# Sheet8.net
KiCad netlist of a schematic drawn in Altium Designer
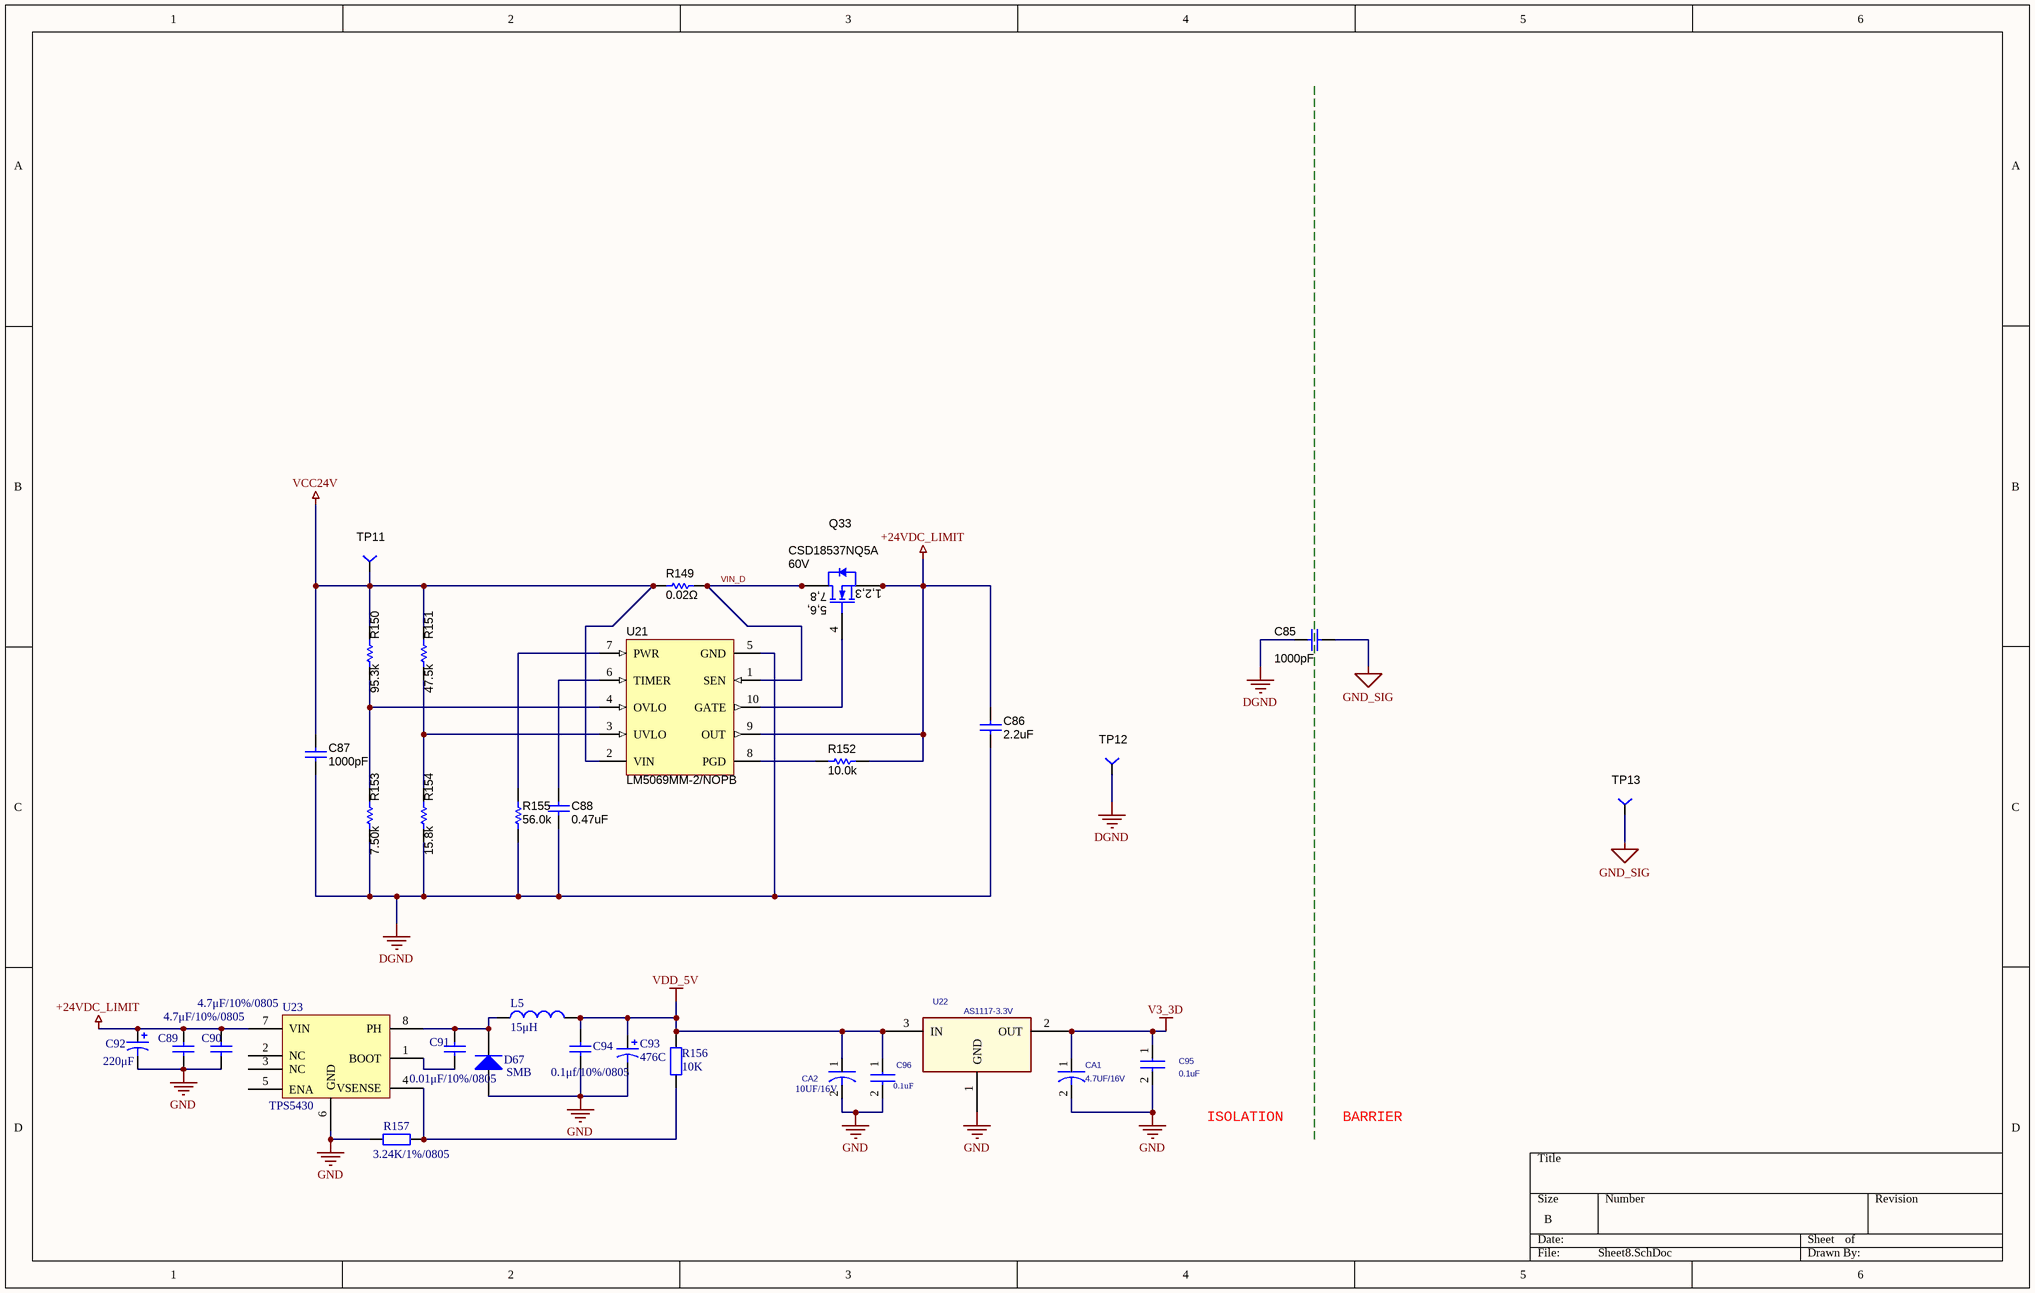
[diagram p0: Sheet8.SchDoc]

(export (version "E")
  (design (tool "Eeschema 10.0.6"))
  (components
    (comp (ref "C85")
      (value "1000pF")
      (footprint "1206")
      (description "CAP, CERM, 1000pF, 2KV 10% X7R 1206")
      (fields
        (field (name "PARTNUMBER") "202R18W102KV4E")
        (field (name "MANUFACTURER") "Johanson Dielectrics Inc")
        (field (name "PUBLISHER") "Texas Instruments")
      )
      (libsource (lib "TI-INDIA-ALTIUM") (part "202R18W102KV4E"))
    )
    (comp (ref "C86")
      (value "GRM32ER72A225KA35L")
      (footprint "1210")
      (description "CAP, CERM, 2.2uF, 100V, +/-10%, X7R, 1210")
      (fields
        (field (name "VALUEDISPLAYED") "2.2uF")
        (field (name "MANUFACTURER") "MuRata")
        (field (name "PUBLISHER") "Texas Instruments")
      )
      (libsource (lib "Capacitor_Ceramic") (part "GRM32ER72A225KA35L"))
    )
    (comp (ref "C87")
      (value "06031C102JAT2A")
      (footprint "0805_cap")
      (description "CAP, CERM, 1000pF, 100V, +/-5%, X7R, 0603")
      (fields
        (field (name "VALUEDISPLAYED") "1000pF")
        (field (name "MANUFACTURER") "AVX")
        (field (name "PUBLISHER") "Texas Instruments")
      )
      (libsource (lib "Capacitor_Ceramic") (part "06031C102JAT2A"))
    )
    (comp (ref "C88")
      (value "UMK107ABJ474KA-T")
      (footprint "0805_cap")
      (description "CAP, CERM, 0.47uF, 50V, 10%, X5R, 0603")
      (fields
        (field (name "MANUFACTURER") "Taiyo Yuden")
        (field (name "VALUEDISPLAYED") "0.47uF")
        (field (name "PUBLISHER") "Texas Instruments")
      )
      (libsource (lib "TI-INDIA-ALTIUM") (part "UMK107ABJ474KA-T"))
    )
    (comp (ref "C89")
      (value "4.7μF/10%/0805")
      (footprint "0805_CAP")
      (description "Capacitor")
      (fields (field (name "PUBLISHER") "Altium Limited"))
      (libsource (lib "Miscellaneous Devices") (part "Cap"))
    )
    (comp (ref "C90")
      (value "4.7μF/10%/0805")
      (footprint "0805_CAP")
      (description "Capacitor")
      (fields (field (name "PUBLISHER") "Altium Limited"))
      (libsource (lib "Miscellaneous Devices") (part "Cap"))
    )
    (comp (ref "C91")
      (value "0.01μF/10%/0805")
      (footprint "0805_CAP")
      (description "Capacitor")
      (fields (field (name "PUBLISHER") "Altium Limited"))
      (libsource (lib "Miscellaneous Devices") (part "Cap"))
    )
    (comp (ref "C92")
      (value "220μF")
      (footprint "CZ3.0/6.5")
      (description "Polarized Capacitor (Radial)")
      (fields (field (name "PUBLISHER") "Altium Limited"))
      (libsource (lib "Miscellaneous Devices") (part "Cap Pol1"))
    )
    (comp (ref "C93")
      (value "476C")
      (footprint "7343-43")
      (description "Polarized Capacitor (Radial)")
      (fields (field (name "PUBLISHER") "Altium Limited"))
      (libsource (lib "Miscellaneous Devices") (part "Cap Pol1"))
    )
    (comp (ref "C94")
      (value "0.1μf/10%/0805")
      (footprint "0805_CAP")
      (description "Capacitor")
      (fields (field (name "PUBLISHER") "Altium Limited"))
      (libsource (lib "Miscellaneous Devices") (part "Cap"))
    )
    (comp (ref "C95") (value "0.1uF") (footprint "0805_CAP") (libsource (lib "v3") (part "C")))
    (comp (ref "C96") (value "0.1uF") (footprint "0805_CAP") (libsource (lib "v3") (part "C")))
    (comp (ref "CA1") (value "4.7UF/16V") (footprint "3528cap") (libsource (lib "v3") (part "ECAP")))
    (comp (ref "CA2") (value "10UF/16V") (footprint "3528cap") (libsource (lib "v3") (part "ECAP")))
    (comp (ref "D67")
      (value "SMB")
      (footprint "SMB")
      (description "3 Amp Medium Power Silicon Rectifier Diode")
      (fields (field (name "PUBLISHER") "Altium Limited"))
      (libsource (lib "Miscellaneous Devices") (part "Diode 1N5408"))
    )
    (comp (ref "L5")
      (value "15μH")
      (footprint "GSDS104C2")
      (description "Inductor")
      (fields (field (name "PUBLISHER") "Altium Limited"))
      (libsource (lib "Miscellaneous Devices") (part "Inductor"))
    )
    (comp (ref "Q33")
      (value "CSD18537NQ5A")
      (footprint "TRANS_NexFET_Q5A")
      (description "MOSFET, N-CH, 60V, 50A, SON 5x6mm")
      (fields
        (field (name "ALTIUM_VALUE") "60V")
        (field (name "MANUFACTURER") "Texas Instruments")
        (field (name "PUBLISHER") "Texas Instruments")
      )
      (libsource (lib "FETs") (part "CSD18537NQ5A"))
    )
    (comp (ref "R149")
      (value "0.02Ω")
      (footprint "1206")
      (description "RES, 0.02 ohm, 1%, 1W, 1206")
      (fields
        (field (name "PARTNUMBER") "PRL1632-R020-F-T1")
        (field (name "MANUFACTURER") "Susumu Co Ltd")
        (field (name "PUBLISHER") "Texas Instruments")
      )
      (libsource (lib "Resistor_1206") (part "PRL1632-R020-F-T1"))
    )
    (comp (ref "R150")
      (value "95.3k")
      (footprint "0805")
      (description "RES, 95.3k ohm, 1%, 0.1W, 0603")
      (fields
        (field (name "PARTNUMBER") "CRCW060395K3FKEA")
        (field (name "MANUFACTURER") "Vishay-Dale")
        (field (name "PUBLISHER") "Texas Instruments")
      )
      (libsource (lib "Resistor_0603") (part "CRCW060395K3FKEA"))
    )
    (comp (ref "R151")
      (value "47.5k")
      (footprint "0805")
      (description "RES, 47.5k ohm, 1%, 0.1W, 0603")
      (fields
        (field (name "PARTNUMBER") "CRCW060347K5FKEA")
        (field (name "MANUFACTURER") "Vishay-Dale")
        (field (name "PUBLISHER") "Texas Instruments")
      )
      (libsource (lib "Resistor_0603") (part "CRCW060347K5FKEA"))
    )
    (comp (ref "R152")
      (value "10.0k")
      (footprint "0805")
      (description "RES, 10.0k ohm, 1%, 0.1W, 0603")
      (fields
        (field (name "PARTNUMBER") "CRCW060310K0FKEA")
        (field (name "MANUFACTURER") "Vishay-Dale")
        (field (name "PUBLISHER") "Texas Instruments")
      )
      (libsource (lib "Resistor_0603") (part "CRCW060310K0FKEA"))
    )
    (comp (ref "R153")
      (value "7.50k")
      (footprint "0805")
      (description "RES, 7.50k ohm, 1%, 0.1W, 0603")
      (fields
        (field (name "PARTNUMBER") "CRCW06037K50FKEA")
        (field (name "MANUFACTURER") "Vishay-Dale")
        (field (name "PUBLISHER") "Texas Instruments")
      )
      (libsource (lib "Resistor_0603") (part "CRCW06037K50FKEA"))
    )
    (comp (ref "R154")
      (value "15.8k")
      (footprint "0805")
      (description "RES, 15.8k ohm, 1%, 0.1W, 0603")
      (fields
        (field (name "PARTNUMBER") "CRCW060315K8FKEA")
        (field (name "MANUFACTURER") "Vishay-Dale")
        (field (name "PUBLISHER") "Texas Instruments")
      )
      (libsource (lib "Resistor_0603") (part "CRCW060315K8FKEA"))
    )
    (comp (ref "R155")
      (value "56.0k")
      (footprint "0805")
      (description "RES, 56.0k ohm, 0.1%, 0.1W, 0603")
      (fields
        (field (name "PARTNUMBER") "RG1608P-563-B-T5")
        (field (name "MANUFACTURER") "Susumu Co Ltd")
        (field (name "PUBLISHER") "Texas Instruments")
      )
      (libsource (lib "Resistor_0603") (part "RG1608P-563-B-T5"))
    )
    (comp (ref "R156")
      (value "10K")
      (footprint "0805")
      (description "Resistor")
      (fields (field (name "PUBLISHER") "Altium Limited"))
      (libsource (lib "Miscellaneous Devices") (part "Res2"))
    )
    (comp (ref "R157")
      (value "3.24K/1%/0805")
      (footprint "0805")
      (description "Resistor")
      (fields (field (name "PUBLISHER") "Altium Limited"))
      (libsource (lib "") (part "Res2_1"))
    )
    (comp (ref "TP11")
      (value "TP-040_RND")
      (footprint "TP-040_RND")
      (description "Test Point, O.040 Hole")
      (fields (field (name "MANUFACTURER") "Standard"))
      (libsource (lib "PADSlegacy_Hardware") (part "TP-040_RND"))
    )
    (comp (ref "TP12")
      (value "TP-040_RND")
      (footprint "TP-040_RND")
      (description "Test Point, O.040 Hole")
      (fields (field (name "MANUFACTURER") "Standard"))
      (libsource (lib "PADSlegacy_Hardware") (part "TP-040_RND"))
    )
    (comp (ref "TP13")
      (value "TP-040_RND")
      (footprint "TP-040_RND")
      (description "Test Point, O.040 Hole")
      (fields (field (name "MANUFACTURER") "Standard"))
      (libsource (lib "PADSlegacy_Hardware") (part "TP-040_RND"))
    )
    (comp (ref "U21")
      (value "LM5069MM-2/NOPB")
      (footprint "MUB10A_N")
      (fields
        (field (name "MANUFACTURER") "National Semiconductor")
        (field (name "PUBLISHER") "Altium Limited")
      )
      (libsource (lib "NSC MiscPower") (part "LM5069MM-2/NOPB"))
    )
    (comp (ref "U22") (value "AS1117-3.3V") (libsource (lib "v3") (part "AS1117")))
    (comp (ref "U23") (value "TPS5430") (footprint "SO-G8") (libsource (lib "SCHLIBRARIES") (part "TPS5430")))
  )
  (nets
    (net (code "1") (name "+24VDC_LIMIT") (class "Default")
      (node (ref "C86") (pin "1") (pinfunction "1_1") (pintype "passive"))
      (node (ref "C89") (pin "2") (pinfunction "2_2") (pintype "passive"))
      (node (ref "C90") (pin "2") (pinfunction "2_2") (pintype "passive"))
      (node (ref "C92") (pin "1") (pinfunction "1_1") (pintype "passive"))
      (node (ref "Q33") (pin "1") (pinfunction "S_1") (pintype "passive"))
      (node (ref "Q33") (pin "2") (pinfunction "S_2") (pintype "passive"))
      (node (ref "Q33") (pin "3") (pinfunction "S_3") (pintype "passive"))
      (node (ref "R152") (pin "1") (pinfunction "1_1") (pintype "passive"))
      (node (ref "U21") (pin "9") (pinfunction "OUT_9") (pintype "output"))
      (node (ref "U23") (pin "7") (pinfunction "VIN_7") (pintype "passive"))
    )
    (net (code "2") (name "/VIN_D") (class "Default")
      (node (ref "Q33") (pin "5") (pinfunction "D_5") (pintype "passive"))
      (node (ref "Q33") (pin "6") (pinfunction "D_6") (pintype "passive"))
      (node (ref "Q33") (pin "7") (pinfunction "D_7") (pintype "passive"))
      (node (ref "Q33") (pin "8") (pinfunction "D_8") (pintype "passive"))
      (node (ref "Q33") (pin "9") (pinfunction "D_9") (pintype "passive"))
      (node (ref "R149") (pin "2") (pinfunction "2_2") (pintype "passive"))
      (node (ref "U21") (pin "1") (pinfunction "SEN_1") (pintype "input"))
    )
    (net (code "3") (name "DGND") (class "Default")
      (node (ref "C85") (pin "1") (pinfunction "1_1") (pintype "passive"))
      (node (ref "C86") (pin "2") (pinfunction "2_2") (pintype "passive"))
      (node (ref "C87") (pin "2") (pinfunction "2_2") (pintype "passive"))
      (node (ref "C88") (pin "2") (pinfunction "2_2") (pintype "passive"))
      (node (ref "R153") (pin "1") (pinfunction "1_1") (pintype "passive"))
      (node (ref "R154") (pin "1") (pinfunction "1_1") (pintype "passive"))
      (node (ref "R155") (pin "1") (pinfunction "1_1") (pintype "passive"))
      (node (ref "TP12") (pin "1") (pinfunction "1_1") (pintype "passive"))
      (node (ref "U21") (pin "5") (pinfunction "GND_5") (pintype "power_in"))
    )
    (net (code "4") (name "GND") (class "Default")
      (node (ref "C89") (pin "1") (pinfunction "1_1") (pintype "passive"))
      (node (ref "C90") (pin "1") (pinfunction "1_1") (pintype "passive"))
      (node (ref "C92") (pin "2") (pinfunction "2_2") (pintype "passive"))
      (node (ref "C93") (pin "2") (pinfunction "2_2") (pintype "passive"))
      (node (ref "C94") (pin "1") (pinfunction "1_1") (pintype "passive"))
      (node (ref "C95") (pin "2") (pinfunction "2_2") (pintype "passive"))
      (node (ref "C96") (pin "2") (pinfunction "2_2") (pintype "passive"))
      (node (ref "CA1") (pin "2") (pinfunction "2_2") (pintype "passive"))
      (node (ref "CA2") (pin "2") (pinfunction "2_2") (pintype "passive"))
      (node (ref "D67") (pin "1") (pinfunction "A_1") (pintype "passive"))
      (node (ref "R157") (pin "2") (pinfunction "2_2") (pintype "passive"))
      (node (ref "U22") (pin "1") (pinfunction "GND_1") (pintype "passive"))
      (node (ref "U23") (pin "6") (pinfunction "GND_6") (pintype "passive"))
    )
    (net (code "5") (name "GND_SIG") (class "Default")
      (node (ref "C85") (pin "2") (pinfunction "2_2") (pintype "passive"))
      (node (ref "TP13") (pin "1") (pinfunction "1_1") (pintype "passive"))
    )
    (net (code "6") (name "Net-(D67-K)") (class "Default")
      (node (ref "C91") (pin "2") (pinfunction "2_2") (pintype "passive"))
      (node (ref "D67") (pin "2") (pinfunction "K_2") (pintype "passive"))
      (node (ref "L5") (pin "1") (pinfunction "1_1") (pintype "passive"))
      (node (ref "U23") (pin "8") (pinfunction "PH_8") (pintype "passive"))
    )
    (net (code "7") (name "Net-(Q33-G)") (class "Default")
      (node (ref "Q33") (pin "4") (pinfunction "G_4") (pintype "passive"))
      (node (ref "U21") (pin "10") (pinfunction "GATE_10") (pintype "output"))
    )
    (net (code "8") (name "Net-(U21-OVLO)") (class "Default")
      (node (ref "R150") (pin "1") (pinfunction "1_1") (pintype "passive"))
      (node (ref "R153") (pin "2") (pinfunction "2_2") (pintype "passive"))
      (node (ref "U21") (pin "4") (pinfunction "OVLO_4") (pintype "input"))
    )
    (net (code "9") (name "Net-(U21-PGD)") (class "Default")
      (node (ref "R152") (pin "2") (pinfunction "2_2") (pintype "passive"))
      (node (ref "U21") (pin "8") (pinfunction "PGD_8") (pintype "open_collector"))
    )
    (net (code "10") (name "Net-(U21-PWR)") (class "Default")
      (node (ref "R155") (pin "2") (pinfunction "2_2") (pintype "passive"))
      (node (ref "U21") (pin "7") (pinfunction "PWR_7") (pintype "input"))
    )
    (net (code "11") (name "Net-(U21-TIMER)") (class "Default")
      (node (ref "C88") (pin "1") (pinfunction "1_1") (pintype "passive"))
      (node (ref "U21") (pin "6") (pinfunction "TIMER_6") (pintype "input"))
    )
    (net (code "12") (name "Net-(U21-UVLO)") (class "Default")
      (node (ref "R151") (pin "1") (pinfunction "1_1") (pintype "passive"))
      (node (ref "R154") (pin "2") (pinfunction "2_2") (pintype "passive"))
      (node (ref "U21") (pin "3") (pinfunction "UVLO_3") (pintype "input"))
    )
    (net (code "13") (name "Net-(U23-BOOT)") (class "Default")
      (node (ref "C91") (pin "1") (pinfunction "1_1") (pintype "passive"))
      (node (ref "U23") (pin "1") (pinfunction "BOOT_1") (pintype "passive"))
    )
    (net (code "14") (name "Net-(U23-VSENSE)") (class "Default")
      (node (ref "R156") (pin "1") (pinfunction "1_1") (pintype "passive"))
      (node (ref "R157") (pin "1") (pinfunction "1_1") (pintype "passive"))
      (node (ref "U23") (pin "4") (pinfunction "VSENSE_4") (pintype "passive"))
    )
    (net (code "15") (name "V3_3D") (class "Default")
      (node (ref "C95") (pin "1") (pinfunction "1_1") (pintype "passive"))
      (node (ref "CA1") (pin "1") (pinfunction "1_1") (pintype "passive"))
      (node (ref "U22") (pin "2") (pinfunction "OUT_2") (pintype "passive"))
    )
    (net (code "16") (name "VCC24V") (class "Default")
      (node (ref "C87") (pin "1") (pinfunction "1_1") (pintype "passive"))
      (node (ref "R149") (pin "1") (pinfunction "1_1") (pintype "passive"))
      (node (ref "R150") (pin "2") (pinfunction "2_2") (pintype "passive"))
      (node (ref "R151") (pin "2") (pinfunction "2_2") (pintype "passive"))
      (node (ref "TP11") (pin "1") (pinfunction "1_1") (pintype "passive"))
      (node (ref "U21") (pin "2") (pinfunction "VIN_2") (pintype "power_in"))
    )
    (net (code "17") (name "VDD_5V") (class "Default")
      (node (ref "C93") (pin "1") (pinfunction "1_1") (pintype "passive"))
      (node (ref "C94") (pin "2") (pinfunction "2_2") (pintype "passive"))
      (node (ref "C96") (pin "1") (pinfunction "1_1") (pintype "passive"))
      (node (ref "CA2") (pin "1") (pinfunction "1_1") (pintype "passive"))
      (node (ref "L5") (pin "2") (pinfunction "2_2") (pintype "passive"))
      (node (ref "R156") (pin "2") (pinfunction "2_2") (pintype "passive"))
      (node (ref "U22") (pin "3") (pinfunction "IN_3") (pintype "passive"))
    )
    (net (code "18") (name "unconnected-(U23-ENA-Pad5)") (class "Default")
      (node (ref "U23") (pin "5") (pinfunction "ENA_5") (pintype "passive"))
    )
    (net (code "19") (name "unconnected-(U23-NC-Pad2)") (class "Default")
      (node (ref "U23") (pin "2") (pinfunction "NC_2") (pintype "passive"))
    )
    (net (code "20") (name "unconnected-(U23-NC-Pad3)") (class "Default")
      (node (ref "U23") (pin "3") (pinfunction "NC_3") (pintype "passive"))
    )
  )
)
